# printer_control.net
KiCad netlist of a schematic drawn in Altium Designer
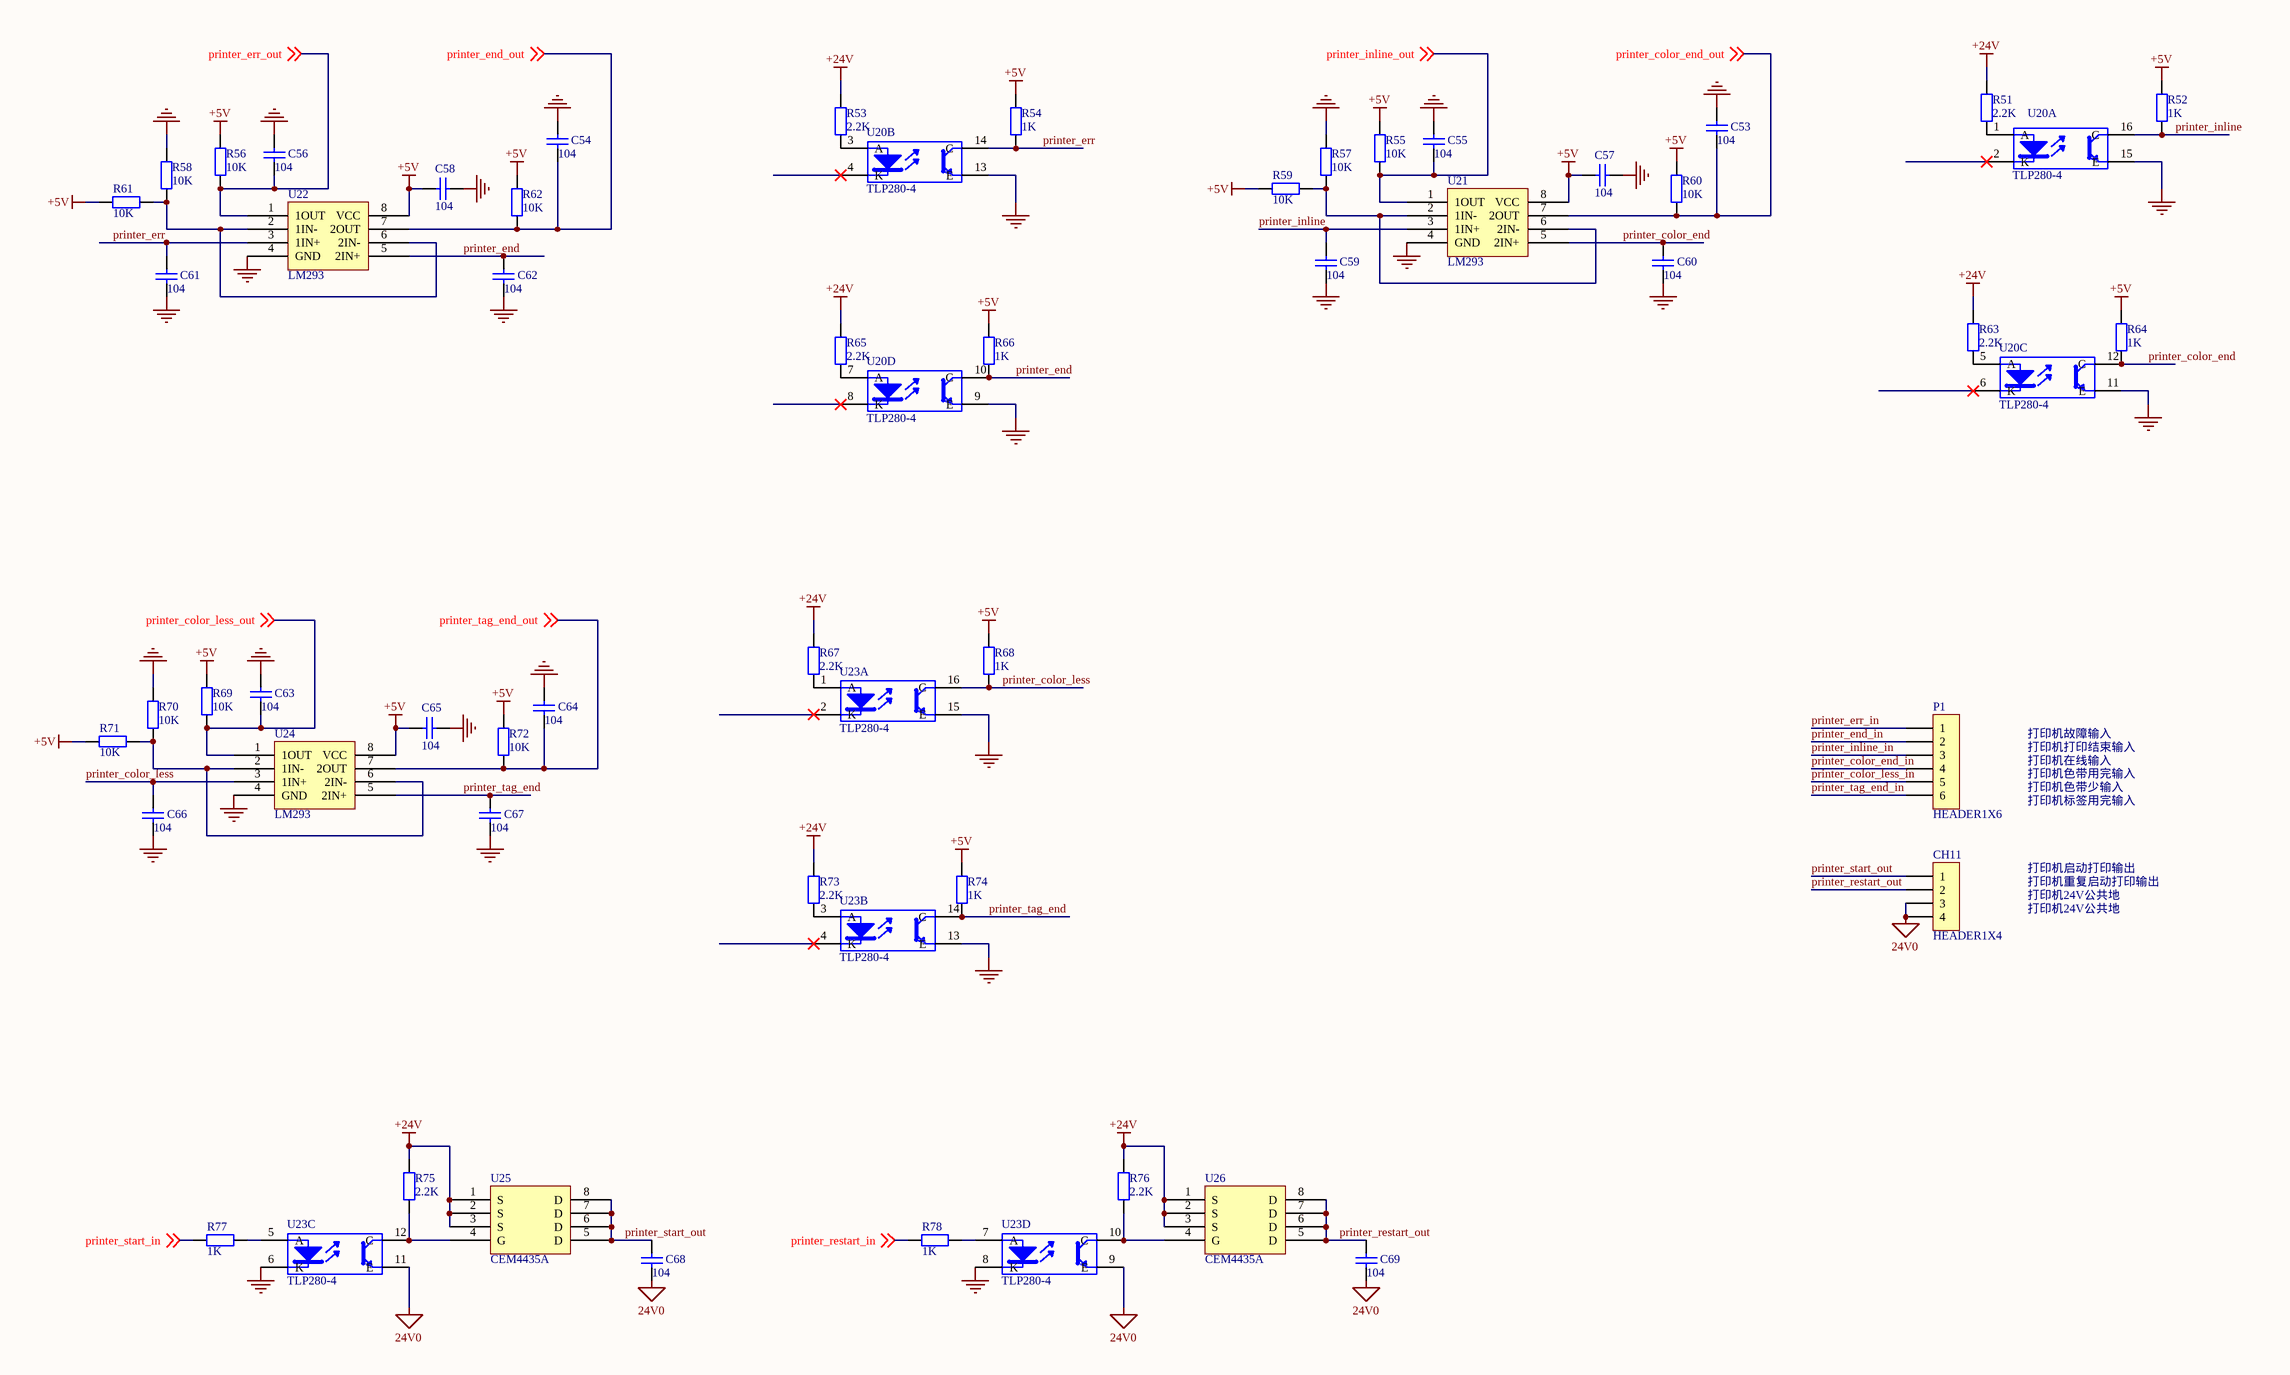
[diagram p0: printer_control.SchDoc]

(export (version "E")
  (design (tool "Eeschema 10.0.6"))
  (components
    (comp (ref "C53")
      (value "104")
      (footprint "0805")
      (description "Capacitor")
      (fields (field (name "Comment") "Cap") (field (name "PUBLISHER") "Altium Limited"))
      (libsource (lib "Miscellaneous Devices") (part "Cap"))
    )
    (comp (ref "C54")
      (value "104")
      (footprint "0805")
      (description "Capacitor")
      (fields (field (name "Comment") "Cap") (field (name "PUBLISHER") "Altium Limited"))
      (libsource (lib "Miscellaneous Devices") (part "Cap"))
    )
    (comp (ref "C55")
      (value "104")
      (footprint "0805")
      (description "Capacitor")
      (fields (field (name "Comment") "Cap") (field (name "PUBLISHER") "Altium Limited"))
      (libsource (lib "Miscellaneous Devices") (part "Cap"))
    )
    (comp (ref "C56")
      (value "104")
      (footprint "0805")
      (description "Capacitor")
      (fields (field (name "Comment") "Cap") (field (name "PUBLISHER") "Altium Limited"))
      (libsource (lib "Miscellaneous Devices") (part "Cap"))
    )
    (comp (ref "C57")
      (value "104")
      (footprint "0805")
      (description "Capacitor")
      (fields (field (name "Comment") "Cap") (field (name "PUBLISHER") "Altium Limited"))
      (libsource (lib "Miscellaneous Devices") (part "Cap"))
    )
    (comp (ref "C58")
      (value "104")
      (footprint "0805")
      (description "Capacitor")
      (fields (field (name "Comment") "Cap") (field (name "PUBLISHER") "Altium Limited"))
      (libsource (lib "Miscellaneous Devices") (part "Cap"))
    )
    (comp (ref "C59")
      (value "104")
      (footprint "0805")
      (description "Capacitor")
      (fields (field (name "Comment") "Cap") (field (name "PUBLISHER") "Altium Limited"))
      (libsource (lib "Miscellaneous Devices") (part "Cap"))
    )
    (comp (ref "C60")
      (value "104")
      (footprint "0805")
      (description "Capacitor")
      (fields (field (name "Comment") "Cap") (field (name "PUBLISHER") "Altium Limited"))
      (libsource (lib "Miscellaneous Devices") (part "Cap"))
    )
    (comp (ref "C61")
      (value "104")
      (footprint "0805")
      (description "Capacitor")
      (fields (field (name "Comment") "Cap") (field (name "PUBLISHER") "Altium Limited"))
      (libsource (lib "Miscellaneous Devices") (part "Cap"))
    )
    (comp (ref "C62")
      (value "104")
      (footprint "0805")
      (description "Capacitor")
      (fields (field (name "Comment") "Cap") (field (name "PUBLISHER") "Altium Limited"))
      (libsource (lib "Miscellaneous Devices") (part "Cap"))
    )
    (comp (ref "C63")
      (value "104")
      (footprint "0805")
      (description "Capacitor")
      (fields (field (name "Comment") "Cap") (field (name "PUBLISHER") "Altium Limited"))
      (libsource (lib "Miscellaneous Devices") (part "Cap"))
    )
    (comp (ref "C64")
      (value "104")
      (footprint "0805")
      (description "Capacitor")
      (fields (field (name "Comment") "Cap") (field (name "PUBLISHER") "Altium Limited"))
      (libsource (lib "Miscellaneous Devices") (part "Cap"))
    )
    (comp (ref "C65")
      (value "104")
      (footprint "0805")
      (description "Capacitor")
      (fields (field (name "Comment") "Cap") (field (name "PUBLISHER") "Altium Limited"))
      (libsource (lib "Miscellaneous Devices") (part "Cap"))
    )
    (comp (ref "C66")
      (value "104")
      (footprint "0805")
      (description "Capacitor")
      (fields (field (name "Comment") "Cap") (field (name "PUBLISHER") "Altium Limited"))
      (libsource (lib "Miscellaneous Devices") (part "Cap"))
    )
    (comp (ref "C67")
      (value "104")
      (footprint "0805")
      (description "Capacitor")
      (fields (field (name "Comment") "Cap") (field (name "PUBLISHER") "Altium Limited"))
      (libsource (lib "Miscellaneous Devices") (part "Cap"))
    )
    (comp (ref "C68")
      (value "104")
      (footprint "0805")
      (description "Capacitor")
      (fields (field (name "Comment") "Cap") (field (name "PUBLISHER") "Altium Limited"))
      (libsource (lib "Miscellaneous Devices") (part "Cap"))
    )
    (comp (ref "C69")
      (value "104")
      (footprint "0805")
      (description "Capacitor")
      (fields (field (name "Comment") "Cap") (field (name "PUBLISHER") "Altium Limited"))
      (libsource (lib "Miscellaneous Devices") (part "Cap"))
    )
    (comp (ref "CH11")
      (value "HEADER1X4")
      (footprint "CH3.96-4PIN")
      (libsource (lib "myIntegrated_Library1") (part "HEADER1X4"))
    )
    (comp (ref "P1")
      (value "HEADER1X6")
      (footprint "CH3.96-6PIN")
      (libsource (lib "myIntegrated_Library1") (part "HEADER1X6"))
    )
    (comp (ref "R51")
      (value "2.2K")
      (footprint "0805")
      (description "Resistor")
      (fields (field (name "Comment") "Res2") (field (name "PUBLISHER") "Altium Limited"))
      (libsource (lib "Miscellaneous Devices") (part "Res2"))
    )
    (comp (ref "R52")
      (value "1K")
      (footprint "0805")
      (description "Resistor")
      (fields (field (name "Comment") "Res2") (field (name "PUBLISHER") "Altium Limited"))
      (libsource (lib "Miscellaneous Devices") (part "Res2"))
    )
    (comp (ref "R53")
      (value "2.2K")
      (footprint "0805")
      (description "Resistor")
      (fields (field (name "Comment") "Res2") (field (name "PUBLISHER") "Altium Limited"))
      (libsource (lib "Miscellaneous Devices") (part "Res2"))
    )
    (comp (ref "R54")
      (value "1K")
      (footprint "0805")
      (description "Resistor")
      (fields (field (name "Comment") "Res2") (field (name "PUBLISHER") "Altium Limited"))
      (libsource (lib "Miscellaneous Devices") (part "Res2"))
    )
    (comp (ref "R55")
      (value "10K")
      (footprint "0805")
      (description "Resistor")
      (fields (field (name "Comment") "Res2") (field (name "PUBLISHER") "Altium Limited"))
      (libsource (lib "Miscellaneous Devices") (part "Res2"))
    )
    (comp (ref "R56")
      (value "10K")
      (footprint "0805")
      (description "Resistor")
      (fields (field (name "Comment") "Res2") (field (name "PUBLISHER") "Altium Limited"))
      (libsource (lib "Miscellaneous Devices") (part "Res2"))
    )
    (comp (ref "R57")
      (value "10K")
      (footprint "0805")
      (description "Resistor")
      (fields (field (name "Comment") "Res2") (field (name "PUBLISHER") "Altium Limited"))
      (libsource (lib "Miscellaneous Devices") (part "Res2"))
    )
    (comp (ref "R58")
      (value "10K")
      (footprint "0805")
      (description "Resistor")
      (fields (field (name "Comment") "Res2") (field (name "PUBLISHER") "Altium Limited"))
      (libsource (lib "Miscellaneous Devices") (part "Res2"))
    )
    (comp (ref "R59")
      (value "10K")
      (footprint "0805")
      (description "Resistor")
      (fields (field (name "Comment") "Res2") (field (name "PUBLISHER") "Altium Limited"))
      (libsource (lib "") (part "Res2_1"))
    )
    (comp (ref "R60")
      (value "10K")
      (footprint "0805")
      (description "Resistor")
      (fields (field (name "Comment") "Res2") (field (name "PUBLISHER") "Altium Limited"))
      (libsource (lib "Miscellaneous Devices") (part "Res2"))
    )
    (comp (ref "R61")
      (value "10K")
      (footprint "0805")
      (description "Resistor")
      (fields (field (name "Comment") "Res2") (field (name "PUBLISHER") "Altium Limited"))
      (libsource (lib "") (part "Res2_1"))
    )
    (comp (ref "R62")
      (value "10K")
      (footprint "0805")
      (description "Resistor")
      (fields (field (name "Comment") "Res2") (field (name "PUBLISHER") "Altium Limited"))
      (libsource (lib "Miscellaneous Devices") (part "Res2"))
    )
    (comp (ref "R63")
      (value "2.2K")
      (footprint "0805")
      (description "Resistor")
      (fields (field (name "Comment") "Res2") (field (name "PUBLISHER") "Altium Limited"))
      (libsource (lib "Miscellaneous Devices") (part "Res2"))
    )
    (comp (ref "R64")
      (value "1K")
      (footprint "0805")
      (description "Resistor")
      (fields (field (name "Comment") "Res2") (field (name "PUBLISHER") "Altium Limited"))
      (libsource (lib "Miscellaneous Devices") (part "Res2"))
    )
    (comp (ref "R65")
      (value "2.2K")
      (footprint "0805")
      (description "Resistor")
      (fields (field (name "Comment") "Res2") (field (name "PUBLISHER") "Altium Limited"))
      (libsource (lib "Miscellaneous Devices") (part "Res2"))
    )
    (comp (ref "R66")
      (value "1K")
      (footprint "0805")
      (description "Resistor")
      (fields (field (name "Comment") "Res2") (field (name "PUBLISHER") "Altium Limited"))
      (libsource (lib "Miscellaneous Devices") (part "Res2"))
    )
    (comp (ref "R67")
      (value "2.2K")
      (footprint "0805")
      (description "Resistor")
      (fields (field (name "Comment") "Res2") (field (name "PUBLISHER") "Altium Limited"))
      (libsource (lib "Miscellaneous Devices") (part "Res2"))
    )
    (comp (ref "R68")
      (value "1K")
      (footprint "0805")
      (description "Resistor")
      (fields (field (name "Comment") "Res2") (field (name "PUBLISHER") "Altium Limited"))
      (libsource (lib "Miscellaneous Devices") (part "Res2"))
    )
    (comp (ref "R69")
      (value "10K")
      (footprint "0805")
      (description "Resistor")
      (fields (field (name "Comment") "Res2") (field (name "PUBLISHER") "Altium Limited"))
      (libsource (lib "Miscellaneous Devices") (part "Res2"))
    )
    (comp (ref "R70")
      (value "10K")
      (footprint "0805")
      (description "Resistor")
      (fields (field (name "Comment") "Res2") (field (name "PUBLISHER") "Altium Limited"))
      (libsource (lib "Miscellaneous Devices") (part "Res2"))
    )
    (comp (ref "R71")
      (value "10K")
      (footprint "0805")
      (description "Resistor")
      (fields (field (name "Comment") "Res2") (field (name "PUBLISHER") "Altium Limited"))
      (libsource (lib "") (part "Res2_1"))
    )
    (comp (ref "R72")
      (value "10K")
      (footprint "0805")
      (description "Resistor")
      (fields (field (name "Comment") "Res2") (field (name "PUBLISHER") "Altium Limited"))
      (libsource (lib "Miscellaneous Devices") (part "Res2"))
    )
    (comp (ref "R73")
      (value "2.2K")
      (footprint "0805")
      (description "Resistor")
      (fields (field (name "Comment") "Res2") (field (name "PUBLISHER") "Altium Limited"))
      (libsource (lib "Miscellaneous Devices") (part "Res2"))
    )
    (comp (ref "R74")
      (value "1K")
      (footprint "0805")
      (description "Resistor")
      (fields (field (name "Comment") "Res2") (field (name "PUBLISHER") "Altium Limited"))
      (libsource (lib "Miscellaneous Devices") (part "Res2"))
    )
    (comp (ref "R75")
      (value "2.2K")
      (footprint "0805")
      (description "Resistor")
      (fields (field (name "Comment") "Res2") (field (name "PUBLISHER") "Altium Limited"))
      (libsource (lib "Miscellaneous Devices") (part "Res2"))
    )
    (comp (ref "R76")
      (value "2.2K")
      (footprint "0805")
      (description "Resistor")
      (fields (field (name "Comment") "Res2") (field (name "PUBLISHER") "Altium Limited"))
      (libsource (lib "Miscellaneous Devices") (part "Res2"))
    )
    (comp (ref "R77")
      (value "1K")
      (footprint "0805")
      (description "Resistor")
      (fields (field (name "Comment") "Res2") (field (name "PUBLISHER") "Altium Limited"))
      (libsource (lib "") (part "Res2_1"))
    )
    (comp (ref "R78")
      (value "1K")
      (footprint "0805")
      (description "Resistor")
      (fields (field (name "Comment") "Res2") (field (name "PUBLISHER") "Altium Limited"))
      (libsource (lib "") (part "Res2_1"))
    )
    (comp (ref "U20") (value "TLP280-4") (footprint "SO16") (libsource (lib "WH V20") (part "TLP521-4")))
    (comp (ref "U21")
      (value "LM293")
      (footprint "SOP8-OP27")
      (libsource (lib "myIntegrated_Library1") (part "LM293"))
    )
    (comp (ref "U22")
      (value "LM293")
      (footprint "SOP8-OP27")
      (libsource (lib "myIntegrated_Library1") (part "LM293"))
    )
    (comp (ref "U23") (value "TLP280-4") (footprint "SO16") (libsource (lib "WH V20") (part "TLP521-4")))
    (comp (ref "U24")
      (value "LM293")
      (footprint "SOP8-OP27")
      (libsource (lib "myIntegrated_Library1") (part "LM293"))
    )
    (comp (ref "U25")
      (value "CEM4435A")
      (footprint "SOP8-OP27")
      (libsource (lib "myIntegrated_Library1") (part "CEM4435A"))
    )
    (comp (ref "U26")
      (value "CEM4435A")
      (footprint "SOP8-OP27")
      (libsource (lib "myIntegrated_Library1") (part "CEM4435A"))
    )
  )
  (nets
    (net (code "1") (name "+5V") (class "Default")
      (node (ref "C57") (pin "2") (pinfunction "2_2") (pintype "passive"))
      (node (ref "C58") (pin "2") (pinfunction "2_2") (pintype "passive"))
      (node (ref "C65") (pin "2") (pinfunction "2_2") (pintype "passive"))
      (node (ref "R52") (pin "1") (pinfunction "1_1") (pintype "passive"))
      (node (ref "R54") (pin "1") (pinfunction "1_1") (pintype "passive"))
      (node (ref "R55") (pin "1") (pinfunction "1_1") (pintype "passive"))
      (node (ref "R56") (pin "1") (pinfunction "1_1") (pintype "passive"))
      (node (ref "R59") (pin "1") (pinfunction "1_1") (pintype "passive"))
      (node (ref "R60") (pin "1") (pinfunction "1_1") (pintype "passive"))
      (node (ref "R61") (pin "1") (pinfunction "1_1") (pintype "passive"))
      (node (ref "R62") (pin "1") (pinfunction "1_1") (pintype "passive"))
      (node (ref "R64") (pin "1") (pinfunction "1_1") (pintype "passive"))
      (node (ref "R66") (pin "1") (pinfunction "1_1") (pintype "passive"))
      (node (ref "R68") (pin "1") (pinfunction "1_1") (pintype "passive"))
      (node (ref "R69") (pin "1") (pinfunction "1_1") (pintype "passive"))
      (node (ref "R71") (pin "1") (pinfunction "1_1") (pintype "passive"))
      (node (ref "R72") (pin "1") (pinfunction "1_1") (pintype "passive"))
      (node (ref "R74") (pin "1") (pinfunction "1_1") (pintype "passive"))
      (node (ref "U21") (pin "8") (pinfunction "VCC_8") (pintype "passive"))
      (node (ref "U22") (pin "8") (pinfunction "VCC_8") (pintype "passive"))
      (node (ref "U24") (pin "8") (pinfunction "VCC_8") (pintype "passive"))
    )
    (net (code "2") (name "+24V") (class "Default")
      (node (ref "R51") (pin "1") (pinfunction "1_1") (pintype "passive"))
      (node (ref "R53") (pin "1") (pinfunction "1_1") (pintype "passive"))
      (node (ref "R63") (pin "1") (pinfunction "1_1") (pintype "passive"))
      (node (ref "R65") (pin "1") (pinfunction "1_1") (pintype "passive"))
      (node (ref "R67") (pin "1") (pinfunction "1_1") (pintype "passive"))
      (node (ref "R73") (pin "1") (pinfunction "1_1") (pintype "passive"))
      (node (ref "R75") (pin "1") (pinfunction "1_1") (pintype "passive"))
      (node (ref "R76") (pin "1") (pinfunction "1_1") (pintype "passive"))
      (node (ref "U25") (pin "1") (pinfunction "S_1") (pintype "passive"))
      (node (ref "U25") (pin "2") (pinfunction "S_2") (pintype "passive"))
      (node (ref "U25") (pin "3") (pinfunction "S_3") (pintype "passive"))
      (node (ref "U26") (pin "1") (pinfunction "S_1") (pintype "passive"))
      (node (ref "U26") (pin "2") (pinfunction "S_2") (pintype "passive"))
      (node (ref "U26") (pin "3") (pinfunction "S_3") (pintype "passive"))
    )
    (net (code "3") (name "/printer_color_end") (class "Default")
      (node (ref "C60") (pin "2") (pinfunction "2_2") (pintype "passive"))
      (node (ref "R64") (pin "2") (pinfunction "2_2") (pintype "passive"))
      (node (ref "U20") (pin "12") (pinfunction "C_12") (pintype "passive"))
      (node (ref "U21") (pin "5") (pinfunction "2IN+_5") (pintype "passive"))
    )
    (net (code "4") (name "/printer_color_end_in") (class "Default")
      (node (ref "P1") (pin "4") (pinfunction "4_4") (pintype "passive"))
    )
    (net (code "5") (name "/printer_color_less") (class "Default")
      (node (ref "C66") (pin "2") (pinfunction "2_2") (pintype "passive"))
      (node (ref "R68") (pin "2") (pinfunction "2_2") (pintype "passive"))
      (node (ref "U23") (pin "16") (pinfunction "C_16") (pintype "passive"))
      (node (ref "U24") (pin "3") (pinfunction "1IN+_3") (pintype "passive"))
    )
    (net (code "6") (name "/printer_color_less_in") (class "Default")
      (node (ref "P1") (pin "5") (pinfunction "5_5") (pintype "passive"))
    )
    (net (code "7") (name "/printer_end") (class "Default")
      (node (ref "C62") (pin "2") (pinfunction "2_2") (pintype "passive"))
      (node (ref "R66") (pin "2") (pinfunction "2_2") (pintype "passive"))
      (node (ref "U20") (pin "10") (pinfunction "C_10") (pintype "passive"))
      (node (ref "U22") (pin "5") (pinfunction "2IN+_5") (pintype "passive"))
    )
    (net (code "8") (name "/printer_end_in") (class "Default")
      (node (ref "P1") (pin "2") (pinfunction "2_2") (pintype "passive"))
    )
    (net (code "9") (name "/printer_err") (class "Default")
      (node (ref "C61") (pin "2") (pinfunction "2_2") (pintype "passive"))
      (node (ref "R54") (pin "2") (pinfunction "2_2") (pintype "passive"))
      (node (ref "U20") (pin "14") (pinfunction "C_14") (pintype "passive"))
      (node (ref "U22") (pin "3") (pinfunction "1IN+_3") (pintype "passive"))
    )
    (net (code "10") (name "/printer_err_in") (class "Default")
      (node (ref "P1") (pin "1") (pinfunction "1_1") (pintype "passive"))
    )
    (net (code "11") (name "/printer_inline") (class "Default")
      (node (ref "C59") (pin "2") (pinfunction "2_2") (pintype "passive"))
      (node (ref "R52") (pin "2") (pinfunction "2_2") (pintype "passive"))
      (node (ref "U20") (pin "16") (pinfunction "C_16") (pintype "passive"))
      (node (ref "U21") (pin "3") (pinfunction "1IN+_3") (pintype "passive"))
    )
    (net (code "12") (name "/printer_inline_in") (class "Default")
      (node (ref "P1") (pin "3") (pinfunction "3_3") (pintype "passive"))
    )
    (net (code "13") (name "/printer_restart_out") (class "Default")
      (node (ref "C69") (pin "2") (pinfunction "2_2") (pintype "passive"))
      (node (ref "CH11") (pin "2") (pinfunction "2_2") (pintype "passive"))
      (node (ref "U26") (pin "5") (pinfunction "D_5") (pintype "passive"))
      (node (ref "U26") (pin "6") (pinfunction "D_6") (pintype "passive"))
      (node (ref "U26") (pin "7") (pinfunction "D_7") (pintype "passive"))
      (node (ref "U26") (pin "8") (pinfunction "D_8") (pintype "passive"))
    )
    (net (code "14") (name "/printer_start_out") (class "Default")
      (node (ref "C68") (pin "2") (pinfunction "2_2") (pintype "passive"))
      (node (ref "CH11") (pin "1") (pinfunction "1_1") (pintype "passive"))
      (node (ref "U25") (pin "5") (pinfunction "D_5") (pintype "passive"))
      (node (ref "U25") (pin "6") (pinfunction "D_6") (pintype "passive"))
      (node (ref "U25") (pin "7") (pinfunction "D_7") (pintype "passive"))
      (node (ref "U25") (pin "8") (pinfunction "D_8") (pintype "passive"))
    )
    (net (code "15") (name "/printer_tag_end") (class "Default")
      (node (ref "C67") (pin "2") (pinfunction "2_2") (pintype "passive"))
      (node (ref "R74") (pin "2") (pinfunction "2_2") (pintype "passive"))
      (node (ref "U23") (pin "14") (pinfunction "C_14") (pintype "passive"))
      (node (ref "U24") (pin "5") (pinfunction "2IN+_5") (pintype "passive"))
    )
    (net (code "16") (name "/printer_tag_end_in") (class "Default")
      (node (ref "P1") (pin "6") (pinfunction "6_6") (pintype "passive"))
    )
    (net (code "17") (name "24V0") (class "Default")
      (node (ref "C68") (pin "1") (pinfunction "1_1") (pintype "passive"))
      (node (ref "C69") (pin "1") (pinfunction "1_1") (pintype "passive"))
      (node (ref "CH11") (pin "3") (pinfunction "3_3") (pintype "passive"))
      (node (ref "CH11") (pin "4") (pinfunction "4_4") (pintype "passive"))
      (node (ref "U23") (pin "11") (pinfunction "E_11") (pintype "passive"))
      (node (ref "U23") (pin "9") (pinfunction "E_9") (pintype "passive"))
    )
    (net (code "18") (name "GND") (class "Default")
      (node (ref "C53") (pin "2") (pinfunction "2_2") (pintype "passive"))
      (node (ref "C54") (pin "2") (pinfunction "2_2") (pintype "passive"))
      (node (ref "C55") (pin "2") (pinfunction "2_2") (pintype "passive"))
      (node (ref "C56") (pin "2") (pinfunction "2_2") (pintype "passive"))
      (node (ref "C57") (pin "1") (pinfunction "1_1") (pintype "passive"))
      (node (ref "C58") (pin "1") (pinfunction "1_1") (pintype "passive"))
      (node (ref "C59") (pin "1") (pinfunction "1_1") (pintype "passive"))
      (node (ref "C60") (pin "1") (pinfunction "1_1") (pintype "passive"))
      (node (ref "C61") (pin "1") (pinfunction "1_1") (pintype "passive"))
      (node (ref "C62") (pin "1") (pinfunction "1_1") (pintype "passive"))
      (node (ref "C63") (pin "2") (pinfunction "2_2") (pintype "passive"))
      (node (ref "C64") (pin "2") (pinfunction "2_2") (pintype "passive"))
      (node (ref "C65") (pin "1") (pinfunction "1_1") (pintype "passive"))
      (node (ref "C66") (pin "1") (pinfunction "1_1") (pintype "passive"))
      (node (ref "C67") (pin "1") (pinfunction "1_1") (pintype "passive"))
      (node (ref "R57") (pin "1") (pinfunction "1_1") (pintype "passive"))
      (node (ref "R58") (pin "1") (pinfunction "1_1") (pintype "passive"))
      (node (ref "R70") (pin "1") (pinfunction "1_1") (pintype "passive"))
      (node (ref "U20") (pin "11") (pinfunction "E_11") (pintype "passive"))
      (node (ref "U20") (pin "13") (pinfunction "E_13") (pintype "passive"))
      (node (ref "U20") (pin "15") (pinfunction "E_15") (pintype "passive"))
      (node (ref "U20") (pin "9") (pinfunction "E_9") (pintype "passive"))
      (node (ref "U21") (pin "4") (pinfunction "GND_4") (pintype "passive"))
      (node (ref "U22") (pin "4") (pinfunction "GND_4") (pintype "passive"))
      (node (ref "U23") (pin "13") (pinfunction "E_13") (pintype "passive"))
      (node (ref "U23") (pin "15") (pinfunction "E_15") (pintype "passive"))
      (node (ref "U23") (pin "6") (pinfunction "K_6") (pintype "passive"))
      (node (ref "U23") (pin "8") (pinfunction "K_8") (pintype "passive"))
      (node (ref "U24") (pin "4") (pinfunction "GND_4") (pintype "passive"))
    )
    (net (code "19") (name "Net-(U20A-A)") (class "Default")
      (node (ref "R51") (pin "2") (pinfunction "2_2") (pintype "passive"))
      (node (ref "U20") (pin "1") (pinfunction "A_1") (pintype "passive"))
    )
    (net (code "20") (name "Net-(U20B-A)") (class "Default")
      (node (ref "R53") (pin "2") (pinfunction "2_2") (pintype "passive"))
      (node (ref "U20") (pin "3") (pinfunction "A_3") (pintype "passive"))
    )
    (net (code "21") (name "Net-(U20C-A)") (class "Default")
      (node (ref "R63") (pin "2") (pinfunction "2_2") (pintype "passive"))
      (node (ref "U20") (pin "5") (pinfunction "A_5") (pintype "passive"))
    )
    (net (code "22") (name "Net-(U20D-A)") (class "Default")
      (node (ref "R65") (pin "2") (pinfunction "2_2") (pintype "passive"))
      (node (ref "U20") (pin "7") (pinfunction "A_7") (pintype "passive"))
    )
    (net (code "23") (name "Net-(U21-1IN-)") (class "Default")
      (node (ref "R57") (pin "2") (pinfunction "2_2") (pintype "passive"))
      (node (ref "R59") (pin "2") (pinfunction "2_2") (pintype "passive"))
      (node (ref "U21") (pin "2") (pinfunction "1IN-_2") (pintype "passive"))
      (node (ref "U21") (pin "6") (pinfunction "2IN-_6") (pintype "passive"))
    )
    (net (code "24") (name "Net-(U22-1IN-)") (class "Default")
      (node (ref "R58") (pin "2") (pinfunction "2_2") (pintype "passive"))
      (node (ref "R61") (pin "2") (pinfunction "2_2") (pintype "passive"))
      (node (ref "U22") (pin "2") (pinfunction "1IN-_2") (pintype "passive"))
      (node (ref "U22") (pin "6") (pinfunction "2IN-_6") (pintype "passive"))
    )
    (net (code "25") (name "Net-(U23A-A)") (class "Default")
      (node (ref "R67") (pin "2") (pinfunction "2_2") (pintype "passive"))
      (node (ref "U23") (pin "1") (pinfunction "A_1") (pintype "passive"))
    )
    (net (code "26") (name "Net-(U23B-A)") (class "Default")
      (node (ref "R73") (pin "2") (pinfunction "2_2") (pintype "passive"))
      (node (ref "U23") (pin "3") (pinfunction "A_3") (pintype "passive"))
    )
    (net (code "27") (name "Net-(U23C-A)") (class "Default")
      (node (ref "R77") (pin "2") (pinfunction "2_2") (pintype "passive"))
      (node (ref "U23") (pin "5") (pinfunction "A_5") (pintype "passive"))
    )
    (net (code "28") (name "Net-(U23C-C)") (class "Default")
      (node (ref "R75") (pin "2") (pinfunction "2_2") (pintype "passive"))
      (node (ref "U23") (pin "12") (pinfunction "C_12") (pintype "passive"))
      (node (ref "U25") (pin "4") (pinfunction "G_4") (pintype "passive"))
    )
    (net (code "29") (name "Net-(U23D-A)") (class "Default")
      (node (ref "R78") (pin "2") (pinfunction "2_2") (pintype "passive"))
      (node (ref "U23") (pin "7") (pinfunction "A_7") (pintype "passive"))
    )
    (net (code "30") (name "Net-(U23D-C)") (class "Default")
      (node (ref "R76") (pin "2") (pinfunction "2_2") (pintype "passive"))
      (node (ref "U23") (pin "10") (pinfunction "C_10") (pintype "passive"))
      (node (ref "U26") (pin "4") (pinfunction "G_4") (pintype "passive"))
    )
    (net (code "31") (name "Net-(U24-1IN-)") (class "Default")
      (node (ref "R70") (pin "2") (pinfunction "2_2") (pintype "passive"))
      (node (ref "R71") (pin "2") (pinfunction "2_2") (pintype "passive"))
      (node (ref "U24") (pin "2") (pinfunction "1IN-_2") (pintype "passive"))
      (node (ref "U24") (pin "6") (pinfunction "2IN-_6") (pintype "passive"))
    )
    (net (code "32") (name "printer_color_end_out") (class "Default")
      (node (ref "C53") (pin "1") (pinfunction "1_1") (pintype "passive"))
      (node (ref "R60") (pin "2") (pinfunction "2_2") (pintype "passive"))
      (node (ref "U21") (pin "7") (pinfunction "2OUT_7") (pintype "passive"))
    )
    (net (code "33") (name "printer_color_less_out") (class "Default")
      (node (ref "C63") (pin "1") (pinfunction "1_1") (pintype "passive"))
      (node (ref "R69") (pin "2") (pinfunction "2_2") (pintype "passive"))
      (node (ref "U24") (pin "1") (pinfunction "1OUT_1") (pintype "passive"))
    )
    (net (code "34") (name "printer_end_out") (class "Default")
      (node (ref "C54") (pin "1") (pinfunction "1_1") (pintype "passive"))
      (node (ref "R62") (pin "2") (pinfunction "2_2") (pintype "passive"))
      (node (ref "U22") (pin "7") (pinfunction "2OUT_7") (pintype "passive"))
    )
    (net (code "35") (name "printer_err_out") (class "Default")
      (node (ref "C56") (pin "1") (pinfunction "1_1") (pintype "passive"))
      (node (ref "R56") (pin "2") (pinfunction "2_2") (pintype "passive"))
      (node (ref "U22") (pin "1") (pinfunction "1OUT_1") (pintype "passive"))
    )
    (net (code "36") (name "printer_inline_out") (class "Default")
      (node (ref "C55") (pin "1") (pinfunction "1_1") (pintype "passive"))
      (node (ref "R55") (pin "2") (pinfunction "2_2") (pintype "passive"))
      (node (ref "U21") (pin "1") (pinfunction "1OUT_1") (pintype "passive"))
    )
    (net (code "37") (name "printer_restart_in") (class "Default")
      (node (ref "R78") (pin "1") (pinfunction "1_1") (pintype "passive"))
    )
    (net (code "38") (name "printer_start_in") (class "Default")
      (node (ref "R77") (pin "1") (pinfunction "1_1") (pintype "passive"))
    )
    (net (code "39") (name "printer_tag_end_out") (class "Default")
      (node (ref "C64") (pin "1") (pinfunction "1_1") (pintype "passive"))
      (node (ref "R72") (pin "2") (pinfunction "2_2") (pintype "passive"))
      (node (ref "U24") (pin "7") (pinfunction "2OUT_7") (pintype "passive"))
    )
    (net (code "40") (name "unconnected-(U20A-K-Pad2)") (class "Default")
      (node (ref "U20") (pin "2") (pinfunction "K_2") (pintype "passive+no_connect"))
    )
    (net (code "41") (name "unconnected-(U20B-K-Pad4)") (class "Default")
      (node (ref "U20") (pin "4") (pinfunction "K_4") (pintype "passive+no_connect"))
    )
    (net (code "42") (name "unconnected-(U20C-K-Pad6)") (class "Default")
      (node (ref "U20") (pin "6") (pinfunction "K_6") (pintype "passive+no_connect"))
    )
    (net (code "43") (name "unconnected-(U20D-K-Pad8)") (class "Default")
      (node (ref "U20") (pin "8") (pinfunction "K_8") (pintype "passive+no_connect"))
    )
    (net (code "44") (name "unconnected-(U23A-K-Pad2)") (class "Default")
      (node (ref "U23") (pin "2") (pinfunction "K_2") (pintype "passive+no_connect"))
    )
    (net (code "45") (name "unconnected-(U23B-K-Pad4)") (class "Default")
      (node (ref "U23") (pin "4") (pinfunction "K_4") (pintype "passive+no_connect"))
    )
  )
)
